# schema.net
KiCad netlist of a schematic drawn in EAGLE
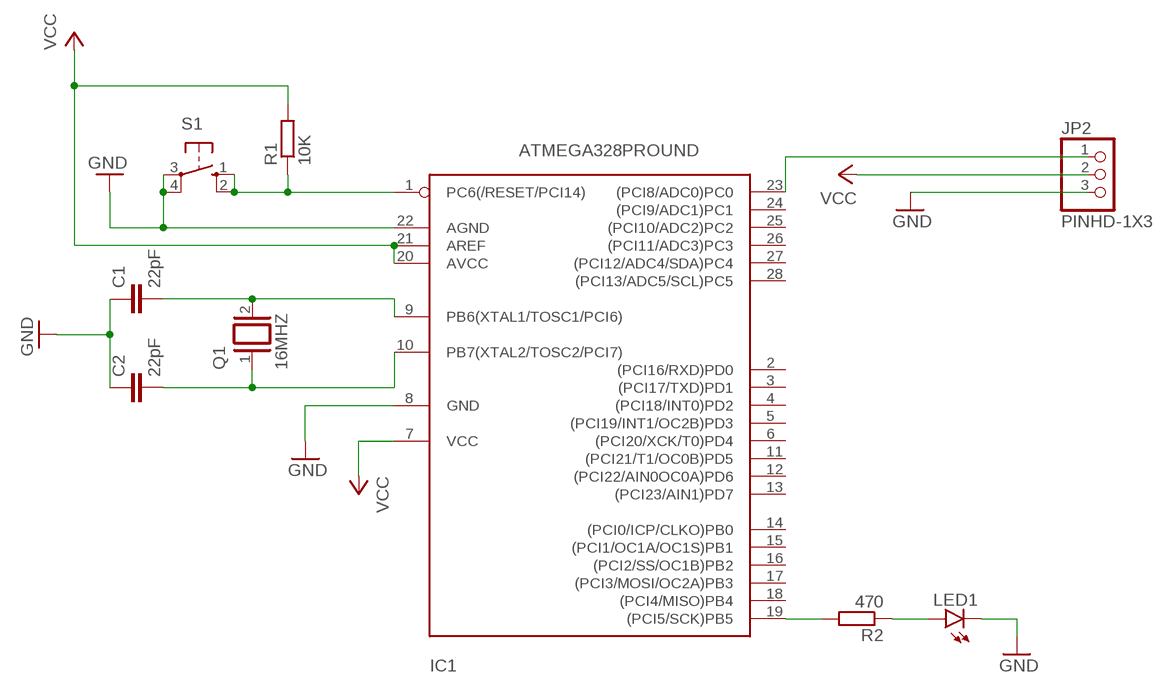
[diagram p0: schematic, sheet 1]

(export (version "E")
  (design (tool "Eeschema 10.0.6"))
  (components
    (comp (ref "C1")
      (value "22pF")
      (footprint "eagle-import:C025-025X050")
      (libsource (lib "eagle-import") (part "C-EU025-025X050"))
    )
    (comp (ref "C2")
      (value "22pF")
      (footprint "eagle-import:C025-025X050")
      (libsource (lib "eagle-import") (part "C-EU025-025X050"))
    )
    (comp (ref "IC1")
      (value "ATMEGA328PROUND")
      (footprint "eagle-import:DIL28-3-ROUND")
      (fields (field (name "SPICEPREFIX") "X"))
      (libsource (lib "eagle-import") (part "ATMEGA328PROUND"))
    )
    (comp (ref "JP2")
      (value "PINHD-1X3")
      (footprint "eagle-import:1X03")
      (fields (field (name "SPICEPREFIX") "J"))
      (libsource (lib "eagle-import") (part "PINHD-1X3"))
    )
    (comp (ref "LED1")
      (value "LED3MM")
      (footprint "eagle-import:LED3MM")
      (libsource (lib "eagle-import") (part "LED3MM"))
    )
    (comp (ref "Q1")
      (value "16MHZ")
      (footprint "eagle-import:QS")
      (libsource (lib "eagle-import") (part "XTAL/S"))
    )
    (comp (ref "R1")
      (value "10K")
      (footprint "eagle-import:0204_7")
      (libsource (lib "eagle-import") (part "R-EU_0204/7"))
    )
    (comp (ref "R2")
      (value "470")
      (footprint "eagle-import:0204_7")
      (libsource (lib "eagle-import") (part "R-EU_0204/7"))
    )
    (comp (ref "S1")
      (value "10-XX")
      (footprint "eagle-import:B3F-10XX")
      (fields (field (name "MPN") "B3F-1000"))
      (libsource (lib "eagle-import") (part "10-XX"))
    )
  )
  (nets
    (net (code "1") (name "GND") (class "Default")
      (node (ref "C1") (pin "1") (pinfunction "1_1") (pintype "passive"))
      (node (ref "C2") (pin "1") (pinfunction "1_1") (pintype "passive"))
      (node (ref "IC1") (pin "22") (pinfunction "AGND_22") (pintype "bidirectional"))
      (node (ref "IC1") (pin "8") (pinfunction "GND_8") (pintype "bidirectional"))
      (node (ref "JP2") (pin "3") (pinfunction "3_3") (pintype "passive"))
      (node (ref "LED1") (pin "K") (pinfunction "C_K") (pintype "passive"))
      (node (ref "S1") (pin "3") (pinfunction "P_3") (pintype "passive"))
      (node (ref "S1") (pin "4") (pinfunction "P1_4") (pintype "passive"))
    )
    (net (code "2") (name "Net-(IC1-(PCI5{slash}SCK)PB5)") (class "Default")
      (node (ref "IC1") (pin "19") (pinfunction "(PCI5/SCK)PB5_19") (pintype "bidirectional"))
      (node (ref "R2") (pin "2") (pinfunction "2_2") (pintype "passive"))
    )
    (net (code "3") (name "Net-(IC1-(PCI8{slash}ADC0)PC0)") (class "Default")
      (node (ref "IC1") (pin "23") (pinfunction "(PCI8/ADC0)PC0_23") (pintype "bidirectional"))
      (node (ref "JP2") (pin "1") (pinfunction "1_1") (pintype "passive"))
    )
    (net (code "4") (name "Net-(IC1-PB6(XTAL1{slash}TOSC1{slash}PCI6))") (class "Default")
      (node (ref "C1") (pin "2") (pinfunction "2_2") (pintype "passive"))
      (node (ref "IC1") (pin "9") (pinfunction "PB6(XTAL1/TOSC1/PCI6)_9") (pintype "bidirectional"))
      (node (ref "Q1") (pin "2") (pinfunction "2_2") (pintype "passive"))
    )
    (net (code "5") (name "Net-(IC1-PB7(XTAL2{slash}TOSC2{slash}PCI7))") (class "Default")
      (node (ref "C2") (pin "2") (pinfunction "2_2") (pintype "passive"))
      (node (ref "IC1") (pin "10") (pinfunction "PB7(XTAL2/TOSC2/PCI7)_10") (pintype "bidirectional"))
      (node (ref "Q1") (pin "1") (pinfunction "1_1") (pintype "passive"))
    )
    (net (code "6") (name "Net-(IC1-PC6({slash}RESET{slash}PCI14))") (class "Default")
      (node (ref "IC1") (pin "1") (pinfunction "PC6(/RESET/PCI14)_1") (pintype "bidirectional"))
      (node (ref "R1") (pin "1") (pinfunction "1_1") (pintype "passive"))
      (node (ref "S1") (pin "1") (pinfunction "S_1") (pintype "passive"))
      (node (ref "S1") (pin "2") (pinfunction "S1_2") (pintype "passive"))
    )
    (net (code "7") (name "Net-(LED1-PadA)") (class "Default")
      (node (ref "LED1") (pin "A") (pinfunction "A_A") (pintype "passive"))
      (node (ref "R2") (pin "1") (pinfunction "1_1") (pintype "passive"))
    )
    (net (code "8") (name "VCC") (class "Default")
      (node (ref "IC1") (pin "20") (pinfunction "AVCC_20") (pintype "bidirectional"))
      (node (ref "IC1") (pin "21") (pinfunction "AREF_21") (pintype "bidirectional"))
      (node (ref "IC1") (pin "7") (pinfunction "VCC_7") (pintype "bidirectional"))
      (node (ref "JP2") (pin "2") (pinfunction "2_2") (pintype "passive"))
      (node (ref "R1") (pin "2") (pinfunction "2_2") (pintype "passive"))
    )
    (net (code "9") (name "unconnected-(IC1-(PCI0{slash}ICP{slash}CLKO)PB0-Pad14)") (class "Default")
      (node (ref "IC1") (pin "14") (pinfunction "(PCI0/ICP/CLKO)PB0_14") (pintype "bidirectional"))
    )
    (net (code "10") (name "unconnected-(IC1-(PCI1{slash}OC1A{slash}OC1S)PB1-Pad15)") (class "Default")
      (node (ref "IC1") (pin "15") (pinfunction "(PCI1/OC1A/OC1S)PB1_15") (pintype "bidirectional"))
    )
    (net (code "11") (name "unconnected-(IC1-(PCI2{slash}SS{slash}OC1B)PB2-Pad16)") (class "Default")
      (node (ref "IC1") (pin "16") (pinfunction "(PCI2/SS/OC1B)PB2_16") (pintype "bidirectional"))
    )
    (net (code "12") (name "unconnected-(IC1-(PCI3{slash}MOSI{slash}OC2A)PB3-Pad17)") (class "Default")
      (node (ref "IC1") (pin "17") (pinfunction "(PCI3/MOSI/OC2A)PB3_17") (pintype "bidirectional"))
    )
    (net (code "13") (name "unconnected-(IC1-(PCI4{slash}MISO)PB4-Pad18)") (class "Default")
      (node (ref "IC1") (pin "18") (pinfunction "(PCI4/MISO)PB4_18") (pintype "bidirectional"))
    )
    (net (code "14") (name "unconnected-(IC1-(PCI9{slash}ADC1)PC1-Pad24)") (class "Default")
      (node (ref "IC1") (pin "24") (pinfunction "(PCI9/ADC1)PC1_24") (pintype "bidirectional"))
    )
    (net (code "15") (name "unconnected-(IC1-(PCI10{slash}ADC2)PC2-Pad25)") (class "Default")
      (node (ref "IC1") (pin "25") (pinfunction "(PCI10/ADC2)PC2_25") (pintype "bidirectional"))
    )
    (net (code "16") (name "unconnected-(IC1-(PCI11{slash}ADC3)PC3-Pad26)") (class "Default")
      (node (ref "IC1") (pin "26") (pinfunction "(PCI11/ADC3)PC3_26") (pintype "bidirectional"))
    )
    (net (code "17") (name "unconnected-(IC1-(PCI12{slash}ADC4{slash}SDA)PC4-Pad27)") (class "Default")
      (node (ref "IC1") (pin "27") (pinfunction "(PCI12/ADC4/SDA)PC4_27") (pintype "bidirectional"))
    )
    (net (code "18") (name "unconnected-(IC1-(PCI13{slash}ADC5{slash}SCL)PC5-Pad28)") (class "Default")
      (node (ref "IC1") (pin "28") (pinfunction "(PCI13/ADC5/SCL)PC5_28") (pintype "bidirectional"))
    )
    (net (code "19") (name "unconnected-(IC1-(PCI16{slash}RXD)PD0-Pad2)") (class "Default")
      (node (ref "IC1") (pin "2") (pinfunction "(PCI16/RXD)PD0_2") (pintype "bidirectional"))
    )
    (net (code "20") (name "unconnected-(IC1-(PCI17{slash}TXD)PD1-Pad3)") (class "Default")
      (node (ref "IC1") (pin "3") (pinfunction "(PCI17/TXD)PD1_3") (pintype "bidirectional"))
    )
    (net (code "21") (name "unconnected-(IC1-(PCI18{slash}INT0)PD2-Pad4)") (class "Default")
      (node (ref "IC1") (pin "4") (pinfunction "(PCI18/INT0)PD2_4") (pintype "bidirectional"))
    )
    (net (code "22") (name "unconnected-(IC1-(PCI19{slash}INT1{slash}OC2B)PD3-Pad5)") (class "Default")
      (node (ref "IC1") (pin "5") (pinfunction "(PCI19/INT1/OC2B)PD3_5") (pintype "bidirectional"))
    )
    (net (code "23") (name "unconnected-(IC1-(PCI20{slash}XCK{slash}T0)PD4-Pad6)") (class "Default")
      (node (ref "IC1") (pin "6") (pinfunction "(PCI20/XCK/T0)PD4_6") (pintype "bidirectional"))
    )
    (net (code "24") (name "unconnected-(IC1-(PCI21{slash}T1{slash}OC0B)PD5-Pad11)") (class "Default")
      (node (ref "IC1") (pin "11") (pinfunction "(PCI21/T1/OC0B)PD5_11") (pintype "bidirectional"))
    )
    (net (code "25") (name "unconnected-(IC1-(PCI22{slash}AIN0OC0A)PD6-Pad12)") (class "Default")
      (node (ref "IC1") (pin "12") (pinfunction "(PCI22/AIN0OC0A)PD6_12") (pintype "bidirectional"))
    )
    (net (code "26") (name "unconnected-(IC1-(PCI23{slash}AIN1)PD7-Pad13)") (class "Default")
      (node (ref "IC1") (pin "13") (pinfunction "(PCI23/AIN1)PD7_13") (pintype "bidirectional"))
    )
  )
)
